# Button.net
KiCad netlist of a schematic drawn in Altium Designer
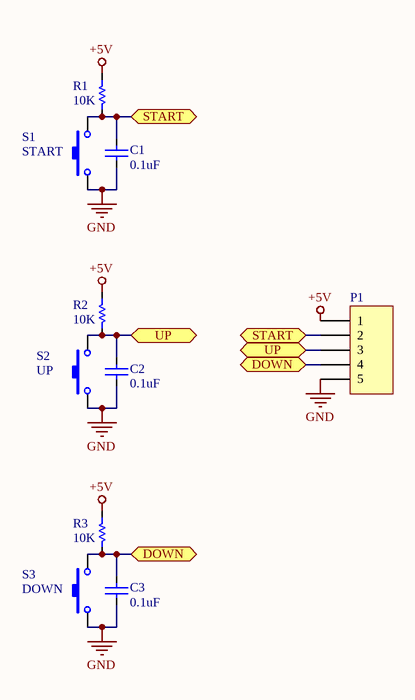
[diagram p0: Button.SchDoc]

(export (version "E")
  (design (tool "Eeschema 10.0.6"))
  (components
    (comp (ref "C1")
      (value "0.1uF")
      (footprint "C0805")
      (description "CAP CER 0.1UF 50V 10% X7R 0805")
      (fields (field (name "DIGI-KEY PART NUMBER") "399-1170-1-ND") (field (name "MANUFACTURER") "Kemet"))
      (libsource (lib "Miscellaneous Devices") (part "Cap"))
    )
    (comp (ref "C2")
      (value "0.1uF")
      (footprint "C0805")
      (description "CAP CER 0.1UF 50V 10% X7R 0805")
      (fields (field (name "DIGI-KEY PART NUMBER") "399-1170-1-ND") (field (name "MANUFACTURER") "Kemet"))
      (libsource (lib "Miscellaneous Devices") (part "Cap"))
    )
    (comp (ref "C3")
      (value "0.1uF")
      (footprint "C0805")
      (description "CAP CER 0.1UF 50V 10% X7R 0805")
      (fields (field (name "DIGI-KEY PART NUMBER") "399-1170-1-ND") (field (name "MANUFACTURER") "Kemet"))
      (libsource (lib "Miscellaneous Devices") (part "Cap"))
    )
    (comp (ref "P1")
      (value "Header 5")
      (footprint "HDR1X5")
      (description "Header, 5-Pin")
      (libsource (lib "Miscellaneous Connectors") (part "Header 5"))
    )
    (comp (ref "R1")
      (value "10K")
      (footprint "R0805")
      (description "RES 10K OHM 1/8W 1% 0805 SMD")
      (fields
        (field (name "MANUFACTURER PART NUMBER") "ERJ-6ENF1002V")
        (field (name "DIGI-KEY PART NUMBER") "P10.0KCCT-ND")
      )
      (libsource (lib "Miscellaneous Devices") (part "Res1"))
    )
    (comp (ref "R2")
      (value "10K")
      (footprint "R0805")
      (description "RES 10K OHM 1/8W 1% 0805 SMD")
      (fields
        (field (name "MANUFACTURER PART NUMBER") "ERJ-6ENF1002V")
        (field (name "DIGI-KEY PART NUMBER") "P10.0KCCT-ND")
      )
      (libsource (lib "Miscellaneous Devices") (part "Res1"))
    )
    (comp (ref "R3")
      (value "10K")
      (footprint "R0805")
      (description "RES 10K OHM 1/8W 1% 0805 SMD")
      (fields
        (field (name "MANUFACTURER PART NUMBER") "ERJ-6ENF1002V")
        (field (name "DIGI-KEY PART NUMBER") "P10.0KCCT-ND")
      )
      (libsource (lib "Miscellaneous Devices") (part "Res1"))
    )
    (comp (ref "S1")
      (value "START")
      (footprint "SWITCH-TACTILE-6mm")
      (description "SWITCH TACTILE SPST-NO 0.05A 12V")
      (fields
        (field (name "MANUFACTURER PART NUMBER") "FSM101")
        (field (name "DIGI-KEY PART NUMBER") "450-1157-ND")
      )
      (libsource (lib "Miscellaneous Devices") (part "SW-PB"))
    )
    (comp (ref "S2")
      (value "UP")
      (footprint "SWITCH-TACTILE-6mm")
      (description "SWITCH TACTILE SPST-NO 0.05A 12V")
      (fields
        (field (name "MANUFACTURER PART NUMBER") "FSM101")
        (field (name "DIGI-KEY PART NUMBER") "450-1157-ND")
      )
      (libsource (lib "Miscellaneous Devices") (part "SW-PB"))
    )
    (comp (ref "S3")
      (value "DOWN")
      (footprint "SWITCH-TACTILE-6mm")
      (description "SWITCH TACTILE SPST-NO 0.05A 12V")
      (fields
        (field (name "MANUFACTURER PART NUMBER") "FSM101")
        (field (name "DIGI-KEY PART NUMBER") "450-1157-ND")
      )
      (libsource (lib "Miscellaneous Devices") (part "SW-PB"))
    )
  )
  (nets
    (net (code "1") (name "+5V") (class "Default")
      (node (ref "P1") (pin "1") (pinfunction "1_1") (pintype "passive"))
      (node (ref "R1") (pin "1") (pinfunction "1_1") (pintype "passive"))
      (node (ref "R2") (pin "1") (pinfunction "1_1") (pintype "passive"))
      (node (ref "R3") (pin "1") (pinfunction "1_1") (pintype "passive"))
    )
    (net (code "2") (name "/DOWN") (class "Default")
      (node (ref "C3") (pin "1") (pinfunction "1_1") (pintype "passive"))
      (node (ref "P1") (pin "4") (pinfunction "4_4") (pintype "passive"))
      (node (ref "R3") (pin "2") (pinfunction "2_2") (pintype "passive"))
      (node (ref "S3") (pin "1") (pinfunction "1_1") (pintype "passive"))
    )
    (net (code "3") (name "/START") (class "Default")
      (node (ref "C1") (pin "1") (pinfunction "1_1") (pintype "passive"))
      (node (ref "P1") (pin "2") (pinfunction "2_2") (pintype "passive"))
      (node (ref "R1") (pin "2") (pinfunction "2_2") (pintype "passive"))
      (node (ref "S1") (pin "1") (pinfunction "1_1") (pintype "passive"))
    )
    (net (code "4") (name "/UP") (class "Default")
      (node (ref "C2") (pin "1") (pinfunction "1_1") (pintype "passive"))
      (node (ref "P1") (pin "3") (pinfunction "3_3") (pintype "passive"))
      (node (ref "R2") (pin "2") (pinfunction "2_2") (pintype "passive"))
      (node (ref "S2") (pin "1") (pinfunction "1_1") (pintype "passive"))
    )
    (net (code "5") (name "GND") (class "Default")
      (node (ref "C1") (pin "2") (pinfunction "2_2") (pintype "passive"))
      (node (ref "C2") (pin "2") (pinfunction "2_2") (pintype "passive"))
      (node (ref "C3") (pin "2") (pinfunction "2_2") (pintype "passive"))
      (node (ref "P1") (pin "5") (pinfunction "5_5") (pintype "passive"))
      (node (ref "S1") (pin "2") (pinfunction "2_2") (pintype "passive"))
      (node (ref "S2") (pin "2") (pinfunction "2_2") (pintype "passive"))
      (node (ref "S3") (pin "2") (pinfunction "2_2") (pintype "passive"))
    )
  )
)
